# M218X.net
KiCad netlist of a schematic drawn in EAGLE
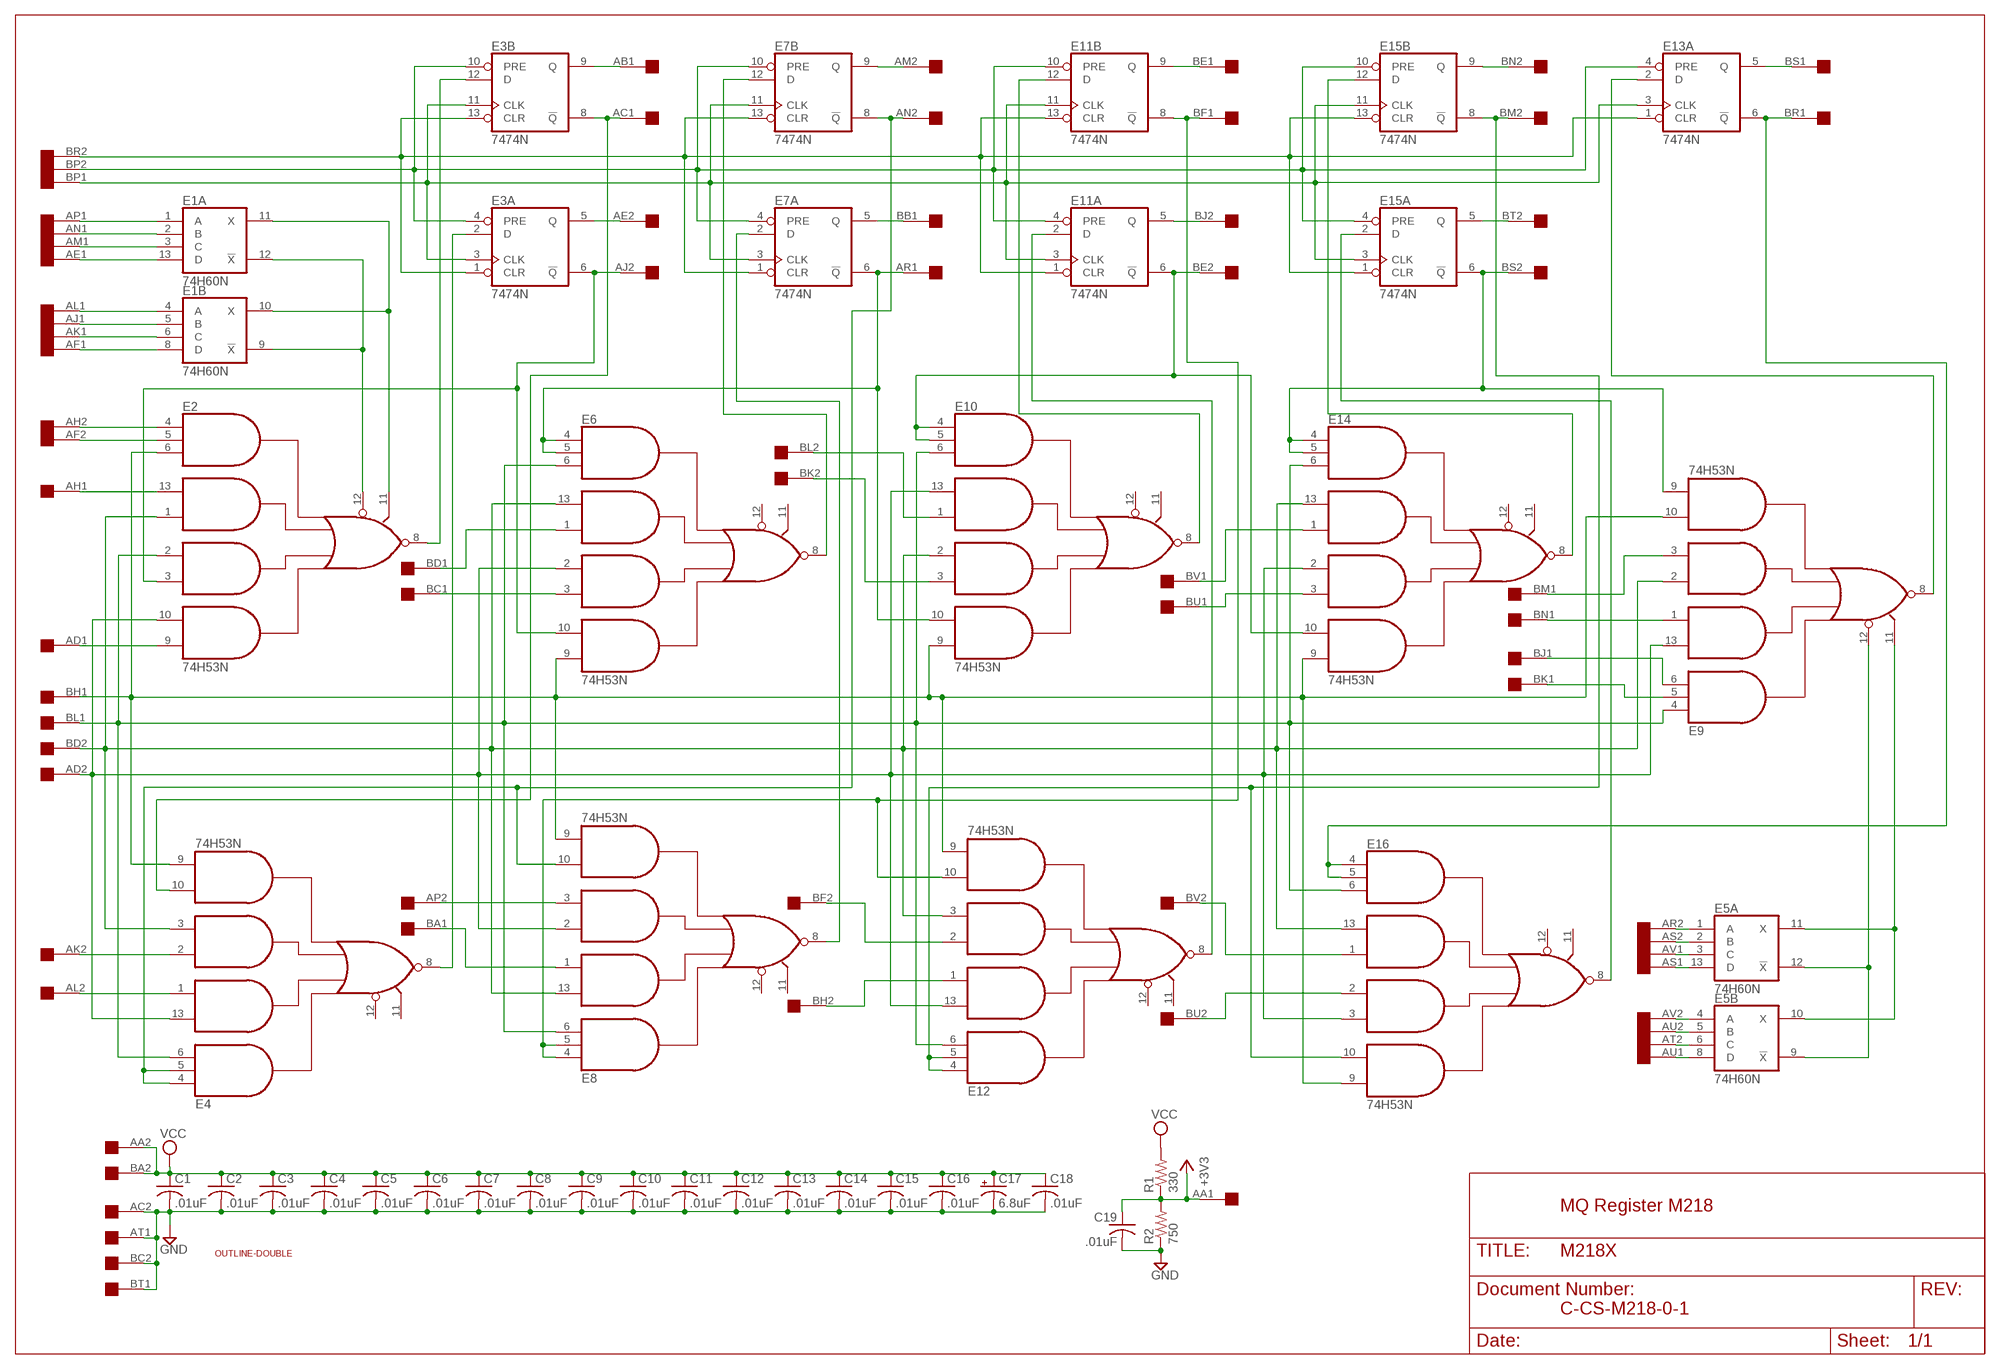
[diagram p0: schematic, sheet 1]

(export (version "E")
  (design (tool "Eeschema 10.0.6"))
  (components
    (comp (ref "C1")
      (value ".01uF")
      (footprint "eagle-import:C050-025X075")
      (libsource (lib "eagle-import") (part "C-US050-025X075"))
    )
    (comp (ref "C2")
      (value ".01uF")
      (footprint "eagle-import:C050-025X075")
      (libsource (lib "eagle-import") (part "C-US050-025X075"))
    )
    (comp (ref "C3")
      (value ".01uF")
      (footprint "eagle-import:C050-025X075")
      (libsource (lib "eagle-import") (part "C-US050-025X075"))
    )
    (comp (ref "C4")
      (value ".01uF")
      (footprint "eagle-import:C050-025X075")
      (libsource (lib "eagle-import") (part "C-US050-025X075"))
    )
    (comp (ref "C5")
      (value ".01uF")
      (footprint "eagle-import:C050-025X075")
      (libsource (lib "eagle-import") (part "C-US050-025X075"))
    )
    (comp (ref "C6")
      (value ".01uF")
      (footprint "eagle-import:C050-025X075")
      (libsource (lib "eagle-import") (part "C-US050-025X075"))
    )
    (comp (ref "C7")
      (value ".01uF")
      (footprint "eagle-import:C050-025X075")
      (libsource (lib "eagle-import") (part "C-US050-025X075"))
    )
    (comp (ref "C8")
      (value ".01uF")
      (footprint "eagle-import:C050-025X075")
      (libsource (lib "eagle-import") (part "C-US050-025X075"))
    )
    (comp (ref "C9")
      (value ".01uF")
      (footprint "eagle-import:C050-025X075")
      (libsource (lib "eagle-import") (part "C-US050-025X075"))
    )
    (comp (ref "C10")
      (value ".01uF")
      (footprint "eagle-import:C050-025X075")
      (libsource (lib "eagle-import") (part "C-US050-025X075"))
    )
    (comp (ref "C11")
      (value ".01uF")
      (footprint "eagle-import:C050-025X075")
      (libsource (lib "eagle-import") (part "C-US050-025X075"))
    )
    (comp (ref "C12")
      (value ".01uF")
      (footprint "eagle-import:C050-025X075")
      (libsource (lib "eagle-import") (part "C-US050-025X075"))
    )
    (comp (ref "C13")
      (value ".01uF")
      (footprint "eagle-import:C050-025X075")
      (libsource (lib "eagle-import") (part "C-US050-025X075"))
    )
    (comp (ref "C14")
      (value ".01uF")
      (footprint "eagle-import:C050-025X075")
      (libsource (lib "eagle-import") (part "C-US050-025X075"))
    )
    (comp (ref "C15")
      (value ".01uF")
      (footprint "eagle-import:C050-025X075")
      (libsource (lib "eagle-import") (part "C-US050-025X075"))
    )
    (comp (ref "C16")
      (value ".01uF")
      (footprint "eagle-import:C050-025X075")
      (libsource (lib "eagle-import") (part "C-US050-025X075"))
    )
    (comp (ref "C17")
      (value "6.8uF")
      (footprint "eagle-import:E12-8")
      (libsource (lib "eagle-import") (part "CPOL-USE20-8AXIAL"))
    )
    (comp (ref "C18")
      (value ".01uF")
      (footprint "eagle-import:C050-025X075")
      (libsource (lib "eagle-import") (part "C-US050-025X075"))
    )
    (comp (ref "C19")
      (value ".01uF")
      (footprint "eagle-import:C050-025X075")
      (libsource (lib "eagle-import") (part "C-US050-025X075"))
    )
    (comp (ref "E1")
      (value "74H60N")
      (footprint "eagle-import:DIL14")
      (libsource (lib "eagle-import") (part "7460N"))
    )
    (comp (ref "E2")
      (value "74H53N")
      (footprint "eagle-import:DIL14")
      (libsource (lib "eagle-import") (part "74H53N"))
    )
    (comp (ref "E3")
      (value "7474N")
      (footprint "eagle-import:DIL14")
      (libsource (lib "eagle-import") (part "7474NS"))
    )
    (comp (ref "E4")
      (value "74H53N")
      (footprint "eagle-import:DIL14")
      (libsource (lib "eagle-import") (part "74H53N"))
    )
    (comp (ref "E5")
      (value "74H60N")
      (footprint "eagle-import:DIL14")
      (libsource (lib "eagle-import") (part "7460N"))
    )
    (comp (ref "E6")
      (value "74H53N")
      (footprint "eagle-import:DIL14")
      (libsource (lib "eagle-import") (part "74H53N"))
    )
    (comp (ref "E7")
      (value "7474N")
      (footprint "eagle-import:DIL14")
      (libsource (lib "eagle-import") (part "7474NS"))
    )
    (comp (ref "E8")
      (value "74H53N")
      (footprint "eagle-import:DIL14")
      (libsource (lib "eagle-import") (part "74H53N"))
    )
    (comp (ref "E9")
      (value "74H53N")
      (footprint "eagle-import:DIL14")
      (libsource (lib "eagle-import") (part "74H53N"))
    )
    (comp (ref "E10")
      (value "74H53N")
      (footprint "eagle-import:DIL14")
      (libsource (lib "eagle-import") (part "74H53N"))
    )
    (comp (ref "E11")
      (value "7474N")
      (footprint "eagle-import:DIL14")
      (libsource (lib "eagle-import") (part "7474NS"))
    )
    (comp (ref "E12")
      (value "74H53N")
      (footprint "eagle-import:DIL14")
      (libsource (lib "eagle-import") (part "74H53N"))
    )
    (comp (ref "E13")
      (value "7474N")
      (footprint "eagle-import:DIL14")
      (libsource (lib "eagle-import") (part "7474NS"))
    )
    (comp (ref "E14")
      (value "74H53N")
      (footprint "eagle-import:DIL14")
      (libsource (lib "eagle-import") (part "74H53N"))
    )
    (comp (ref "E15")
      (value "7474N")
      (footprint "eagle-import:DIL14")
      (libsource (lib "eagle-import") (part "7474NS"))
    )
    (comp (ref "E16")
      (value "74H53N")
      (footprint "eagle-import:DIL14")
      (libsource (lib "eagle-import") (part "74H53N"))
    )
    (comp (ref "R1")
      (value "330")
      (footprint "eagle-import:0207_10")
      (libsource (lib "eagle-import") (part "R-US_0207/10"))
    )
    (comp (ref "R2")
      (value "750")
      (footprint "eagle-import:0207_10")
      (libsource (lib "eagle-import") (part "R-US_0207/10"))
    )
    (comp (ref "U$1")
      (value "OUTLINE-DOUBLE")
      (footprint "eagle-import:DOUBLE")
      (libsource (lib "eagle-import") (part "OUTLINE-DOUBLE"))
    )
    (comp (ref "U$3")
      (value "DOUBLE")
      (footprint "eagle-import:EDGE-CON4")
      (libsource (lib "eagle-import") (part "DOUBLE"))
    )
  )
  (nets
    (net (code "1") (name "+3V3") (class "Default")
      (node (ref "C19") (pin "1") (pinfunction "1_1") (pintype "passive"))
      (node (ref "R1") (pin "1") (pinfunction "1_1") (pintype "passive"))
      (node (ref "R2") (pin "2") (pinfunction "2_2") (pintype "passive"))
      (node (ref "U$3") (pin "AA1") (pinfunction "1_AA1") (pintype "bidirectional"))
    )
    (net (code "2") (name "GND") (class "Default")
      (node (ref "C1") (pin "2") (pinfunction "2_2") (pintype "passive"))
      (node (ref "C10") (pin "2") (pinfunction "2_2") (pintype "passive"))
      (node (ref "C11") (pin "2") (pinfunction "2_2") (pintype "passive"))
      (node (ref "C12") (pin "2") (pinfunction "2_2") (pintype "passive"))
      (node (ref "C13") (pin "2") (pinfunction "2_2") (pintype "passive"))
      (node (ref "C14") (pin "2") (pinfunction "2_2") (pintype "passive"))
      (node (ref "C15") (pin "2") (pinfunction "2_2") (pintype "passive"))
      (node (ref "C16") (pin "2") (pinfunction "2_2") (pintype "passive"))
      (node (ref "C17") (pin "-") (pinfunction "-_-") (pintype "passive"))
      (node (ref "C18") (pin "2") (pinfunction "2_2") (pintype "passive"))
      (node (ref "C19") (pin "2") (pinfunction "2_2") (pintype "passive"))
      (node (ref "C2") (pin "2") (pinfunction "2_2") (pintype "passive"))
      (node (ref "C3") (pin "2") (pinfunction "2_2") (pintype "passive"))
      (node (ref "C4") (pin "2") (pinfunction "2_2") (pintype "passive"))
      (node (ref "C5") (pin "2") (pinfunction "2_2") (pintype "passive"))
      (node (ref "C6") (pin "2") (pinfunction "2_2") (pintype "passive"))
      (node (ref "C7") (pin "2") (pinfunction "2_2") (pintype "passive"))
      (node (ref "C8") (pin "2") (pinfunction "2_2") (pintype "passive"))
      (node (ref "C9") (pin "2") (pinfunction "2_2") (pintype "passive"))
      (node (ref "R2") (pin "1") (pinfunction "1_1") (pintype "passive"))
      (node (ref "U$3") (pin "AC2") (pinfunction "1_AC2") (pintype "bidirectional"))
      (node (ref "U$3") (pin "AT1") (pinfunction "1_AT1") (pintype "bidirectional"))
      (node (ref "U$3") (pin "BC2") (pinfunction "1_BC2") (pintype "bidirectional"))
      (node (ref "U$3") (pin "BT1") (pinfunction "1_BT1") (pintype "bidirectional"))
    )
    (net (code "3") (name "Net-(E1A-A)") (class "Default")
      (node (ref "E1") (pin "1") (pinfunction "A_1") (pintype "input"))
      (node (ref "U$3") (pin "AP1") (pinfunction "1_AP1") (pintype "bidirectional"))
    )
    (net (code "4") (name "Net-(E1A-B)") (class "Default")
      (node (ref "E1") (pin "2") (pinfunction "B_2") (pintype "input"))
      (node (ref "U$3") (pin "AN1") (pinfunction "1_AN1") (pintype "bidirectional"))
    )
    (net (code "5") (name "Net-(E1A-C)") (class "Default")
      (node (ref "E1") (pin "3") (pinfunction "C_3") (pintype "input"))
      (node (ref "U$3") (pin "AM1") (pinfunction "1_AM1") (pintype "bidirectional"))
    )
    (net (code "6") (name "Net-(E1A-D)") (class "Default")
      (node (ref "E1") (pin "13") (pinfunction "D_13") (pintype "input"))
      (node (ref "U$3") (pin "AE1") (pinfunction "1_AE1") (pintype "bidirectional"))
    )
    (net (code "7") (name "Net-(E1A-X)") (class "Default")
      (node (ref "E1") (pin "10") (pinfunction "X_10") (pintype "output"))
      (node (ref "E1") (pin "11") (pinfunction "X_11") (pintype "output"))
      (node (ref "E2") (pin "11") (pinfunction "I10_11") (pintype "passive"))
    )
    (net (code "8") (name "Net-(E1A-~{X})") (class "Default")
      (node (ref "E1") (pin "12") (pinfunction "~{X}_12") (pintype "output"))
      (node (ref "E1") (pin "9") (pinfunction "~{X}_9") (pintype "output"))
      (node (ref "E2") (pin "12") (pinfunction "I9_12") (pintype "passive"))
    )
    (net (code "9") (name "Net-(E1B-A)") (class "Default")
      (node (ref "E1") (pin "4") (pinfunction "A_4") (pintype "input"))
      (node (ref "U$3") (pin "AL1") (pinfunction "1_AL1") (pintype "bidirectional"))
    )
    (net (code "10") (name "Net-(E1B-B)") (class "Default")
      (node (ref "E1") (pin "5") (pinfunction "B_5") (pintype "input"))
      (node (ref "U$3") (pin "AJ1") (pinfunction "1_AJ1") (pintype "bidirectional"))
    )
    (net (code "11") (name "Net-(E1B-C)") (class "Default")
      (node (ref "E1") (pin "6") (pinfunction "C_6") (pintype "input"))
      (node (ref "U$3") (pin "AK1") (pinfunction "1_AK1") (pintype "bidirectional"))
    )
    (net (code "12") (name "Net-(E1B-D)") (class "Default")
      (node (ref "E1") (pin "8") (pinfunction "D_8") (pintype "input"))
      (node (ref "U$3") (pin "AF1") (pinfunction "1_AF1") (pintype "bidirectional"))
    )
    (net (code "13") (name "Net-(E2A-I1)") (class "Default")
      (node (ref "E2") (pin "4") (pinfunction "I1_4") (pintype "input"))
      (node (ref "U$3") (pin "AH2") (pinfunction "1_AH2") (pintype "bidirectional"))
    )
    (net (code "14") (name "Net-(E2A-I3)") (class "Default")
      (node (ref "E2") (pin "13") (pinfunction "I3_13") (pintype "input"))
      (node (ref "U$3") (pin "AH1") (pinfunction "1_AH1") (pintype "bidirectional"))
    )
    (net (code "15") (name "Net-(E2A-I6)") (class "Default")
      (node (ref "E2") (pin "3") (pinfunction "I6_3") (pintype "input"))
      (node (ref "E3") (pin "6") (pinfunction "~{Q}_6") (pintype "output"))
      (node (ref "E6") (pin "10") (pinfunction "I7_10") (pintype "input"))
      (node (ref "U$3") (pin "AJ2") (pinfunction "1_AJ2") (pintype "bidirectional"))
    )
    (net (code "16") (name "Net-(E2A-I8)") (class "Default")
      (node (ref "E2") (pin "9") (pinfunction "I8_9") (pintype "input"))
      (node (ref "U$3") (pin "AD1") (pinfunction "1_AD1") (pintype "bidirectional"))
    )
    (net (code "17") (name "Net-(E2A-I11)") (class "Default")
      (node (ref "E2") (pin "5") (pinfunction "I11_5") (pintype "input"))
      (node (ref "U$3") (pin "AF2") (pinfunction "1_AF2") (pintype "bidirectional"))
    )
    (net (code "18") (name "Net-(E2A-O)") (class "Default")
      (node (ref "E2") (pin "8") (pinfunction "O_8") (pintype "output"))
      (node (ref "E3") (pin "12") (pinfunction "D_12") (pintype "input"))
    )
    (net (code "19") (name "Net-(E3A-D)") (class "Default")
      (node (ref "E3") (pin "2") (pinfunction "D_2") (pintype "input"))
      (node (ref "E4") (pin "8") (pinfunction "O_8") (pintype "output"))
    )
    (net (code "20") (name "Net-(E3A-Q)") (class "Default")
      (node (ref "E3") (pin "5") (pinfunction "Q_5") (pintype "output"))
      (node (ref "U$3") (pin "AE2") (pinfunction "1_AE2") (pintype "bidirectional"))
    )
    (net (code "21") (name "Net-(E3B-Q)") (class "Default")
      (node (ref "E3") (pin "9") (pinfunction "Q_9") (pintype "output"))
      (node (ref "U$3") (pin "AB1") (pinfunction "1_AB1") (pintype "bidirectional"))
    )
    (net (code "22") (name "Net-(E3B-~{Q})") (class "Default")
      (node (ref "E3") (pin "8") (pinfunction "~{Q}_8") (pintype "output"))
      (node (ref "E4") (pin "10") (pinfunction "I7_10") (pintype "input"))
      (node (ref "U$3") (pin "AC1") (pinfunction "1_AC1") (pintype "bidirectional"))
    )
    (net (code "23") (name "Net-(E4A-I1)") (class "Default")
      (node (ref "E4") (pin "4") (pinfunction "I1_4") (pintype "input"))
      (node (ref "E4") (pin "5") (pinfunction "I11_5") (pintype "input"))
      (node (ref "E7") (pin "8") (pinfunction "~{Q}_8") (pintype "output"))
      (node (ref "E8") (pin "10") (pinfunction "I7_10") (pintype "input"))
      (node (ref "U$3") (pin "AN2") (pinfunction "1_AN2") (pintype "bidirectional"))
    )
    (net (code "24") (name "Net-(E4A-I4)") (class "Default")
      (node (ref "E4") (pin "1") (pinfunction "I4_1") (pintype "input"))
      (node (ref "U$3") (pin "AL2") (pinfunction "1_AL2") (pintype "bidirectional"))
    )
    (net (code "25") (name "Net-(E4A-I5)") (class "Default")
      (node (ref "E4") (pin "2") (pinfunction "I5_2") (pintype "input"))
      (node (ref "U$3") (pin "AK2") (pinfunction "1_AK2") (pintype "bidirectional"))
    )
    (net (code "26") (name "Net-(E5A-A)") (class "Default")
      (node (ref "E5") (pin "1") (pinfunction "A_1") (pintype "input"))
      (node (ref "U$3") (pin "AR2") (pinfunction "1_AR2") (pintype "bidirectional"))
    )
    (net (code "27") (name "Net-(E5A-B)") (class "Default")
      (node (ref "E5") (pin "2") (pinfunction "B_2") (pintype "input"))
      (node (ref "U$3") (pin "AS2") (pinfunction "1_AS2") (pintype "bidirectional"))
    )
    (net (code "28") (name "Net-(E5A-C)") (class "Default")
      (node (ref "E5") (pin "3") (pinfunction "C_3") (pintype "input"))
      (node (ref "U$3") (pin "AV1") (pinfunction "1_AV1") (pintype "bidirectional"))
    )
    (net (code "29") (name "Net-(E5A-D)") (class "Default")
      (node (ref "E5") (pin "13") (pinfunction "D_13") (pintype "input"))
      (node (ref "U$3") (pin "AS1") (pinfunction "1_AS1") (pintype "bidirectional"))
    )
    (net (code "30") (name "Net-(E5A-X)") (class "Default")
      (node (ref "E5") (pin "10") (pinfunction "X_10") (pintype "output"))
      (node (ref "E5") (pin "11") (pinfunction "X_11") (pintype "output"))
      (node (ref "E9") (pin "11") (pinfunction "I10_11") (pintype "passive"))
    )
    (net (code "31") (name "Net-(E5A-~{X})") (class "Default")
      (node (ref "E5") (pin "12") (pinfunction "~{X}_12") (pintype "output"))
      (node (ref "E5") (pin "9") (pinfunction "~{X}_9") (pintype "output"))
      (node (ref "E9") (pin "12") (pinfunction "I9_12") (pintype "passive"))
    )
    (net (code "32") (name "Net-(E5B-A)") (class "Default")
      (node (ref "E5") (pin "4") (pinfunction "A_4") (pintype "input"))
      (node (ref "U$3") (pin "AV2") (pinfunction "1_AV2") (pintype "bidirectional"))
    )
    (net (code "33") (name "Net-(E5B-B)") (class "Default")
      (node (ref "E5") (pin "5") (pinfunction "B_5") (pintype "input"))
      (node (ref "U$3") (pin "AU2") (pinfunction "1_AU2") (pintype "bidirectional"))
    )
    (net (code "34") (name "Net-(E5B-C)") (class "Default")
      (node (ref "E5") (pin "6") (pinfunction "C_6") (pintype "input"))
      (node (ref "U$3") (pin "AT2") (pinfunction "1_AT2") (pintype "bidirectional"))
    )
    (net (code "35") (name "Net-(E5B-D)") (class "Default")
      (node (ref "E5") (pin "8") (pinfunction "D_8") (pintype "input"))
      (node (ref "U$3") (pin "AU1") (pinfunction "1_AU1") (pintype "bidirectional"))
    )
    (net (code "36") (name "Net-(E6A-I4)") (class "Default")
      (node (ref "E6") (pin "1") (pinfunction "I4_1") (pintype "input"))
      (node (ref "U$3") (pin "BD1") (pinfunction "1_BD1") (pintype "bidirectional"))
    )
    (net (code "37") (name "Net-(E6A-I6)") (class "Default")
      (node (ref "E6") (pin "3") (pinfunction "I6_3") (pintype "input"))
      (node (ref "U$3") (pin "BC1") (pinfunction "1_BC1") (pintype "bidirectional"))
    )
    (net (code "38") (name "Net-(E6A-O)") (class "Default")
      (node (ref "E6") (pin "8") (pinfunction "O_8") (pintype "output"))
      (node (ref "E7") (pin "12") (pinfunction "D_12") (pintype "input"))
    )
    (net (code "39") (name "Net-(E7A-D)") (class "Default")
      (node (ref "E7") (pin "2") (pinfunction "D_2") (pintype "input"))
      (node (ref "E8") (pin "8") (pinfunction "O_8") (pintype "output"))
    )
    (net (code "40") (name "Net-(E7A-Q)") (class "Default")
      (node (ref "E7") (pin "5") (pinfunction "Q_5") (pintype "output"))
      (node (ref "U$3") (pin "BB1") (pinfunction "1_BB1") (pintype "bidirectional"))
    )
    (net (code "41") (name "Net-(E7B-Q)") (class "Default")
      (node (ref "E7") (pin "9") (pinfunction "Q_9") (pintype "output"))
      (node (ref "U$3") (pin "AM2") (pinfunction "1_AM2") (pintype "bidirectional"))
    )
    (net (code "42") (name "Net-(E8A-I4)") (class "Default")
      (node (ref "E8") (pin "1") (pinfunction "I4_1") (pintype "input"))
      (node (ref "U$3") (pin "BA1") (pinfunction "1_BA1") (pintype "bidirectional"))
    )
    (net (code "43") (name "Net-(E8A-I6)") (class "Default")
      (node (ref "E8") (pin "3") (pinfunction "I6_3") (pintype "input"))
      (node (ref "U$3") (pin "AP2") (pinfunction "1_AP2") (pintype "bidirectional"))
    )
    (net (code "44") (name "Net-(E9A-I2)") (class "Default")
      (node (ref "E9") (pin "6") (pinfunction "I2_6") (pintype "input"))
      (node (ref "U$3") (pin "BJ1") (pinfunction "1_BJ1") (pintype "bidirectional"))
    )
    (net (code "45") (name "Net-(E9A-I4)") (class "Default")
      (node (ref "E9") (pin "1") (pinfunction "I4_1") (pintype "input"))
      (node (ref "U$3") (pin "BN1") (pinfunction "1_BN1") (pintype "bidirectional"))
    )
    (net (code "46") (name "Net-(E9A-I6)") (class "Default")
      (node (ref "E9") (pin "3") (pinfunction "I6_3") (pintype "input"))
      (node (ref "U$3") (pin "BM1") (pinfunction "1_BM1") (pintype "bidirectional"))
    )
    (net (code "47") (name "Net-(E9A-I11)") (class "Default")
      (node (ref "E9") (pin "5") (pinfunction "I11_5") (pintype "input"))
      (node (ref "U$3") (pin "BK1") (pinfunction "1_BK1") (pintype "bidirectional"))
    )
    (net (code "48") (name "Net-(E10A-I1)") (class "Default")
      (node (ref "E10") (pin "4") (pinfunction "I1_4") (pintype "input"))
      (node (ref "E10") (pin "5") (pinfunction "I11_5") (pintype "input"))
      (node (ref "E11") (pin "6") (pinfunction "~{Q}_6") (pintype "output"))
      (node (ref "E14") (pin "10") (pinfunction "I7_10") (pintype "input"))
      (node (ref "U$3") (pin "BE2") (pinfunction "1_BE2") (pintype "bidirectional"))
    )
    (net (code "49") (name "Net-(E10A-I2)") (class "Default")
      (node (ref "E10") (pin "6") (pinfunction "I2_6") (pintype "input"))
      (node (ref "E12") (pin "6") (pinfunction "I2_6") (pintype "input"))
      (node (ref "E14") (pin "6") (pinfunction "I2_6") (pintype "input"))
      (node (ref "E16") (pin "6") (pinfunction "I2_6") (pintype "input"))
      (node (ref "E2") (pin "2") (pinfunction "I5_2") (pintype "input"))
      (node (ref "E4") (pin "6") (pinfunction "I2_6") (pintype "input"))
      (node (ref "E6") (pin "6") (pinfunction "I2_6") (pintype "input"))
      (node (ref "E8") (pin "6") (pinfunction "I2_6") (pintype "input"))
      (node (ref "E9") (pin "4") (pinfunction "I1_4") (pintype "input"))
      (node (ref "U$3") (pin "BL1") (pinfunction "1_BL1") (pintype "bidirectional"))
    )
    (net (code "50") (name "Net-(E10A-I3)") (class "Default")
      (node (ref "E10") (pin "13") (pinfunction "I3_13") (pintype "input"))
      (node (ref "E12") (pin "13") (pinfunction "I3_13") (pintype "input"))
      (node (ref "E14") (pin "2") (pinfunction "I5_2") (pintype "input"))
      (node (ref "E16") (pin "3") (pinfunction "I6_3") (pintype "input"))
      (node (ref "E2") (pin "10") (pinfunction "I7_10") (pintype "input"))
      (node (ref "E4") (pin "13") (pinfunction "I3_13") (pintype "input"))
      (node (ref "E6") (pin "2") (pinfunction "I5_2") (pintype "input"))
      (node (ref "E8") (pin "2") (pinfunction "I5_2") (pintype "input"))
      (node (ref "E9") (pin "13") (pinfunction "I3_13") (pintype "input"))
      (node (ref "U$3") (pin "AD2") (pinfunction "1_AD2") (pintype "bidirectional"))
    )
    (net (code "51") (name "Net-(E10A-I4)") (class "Default")
      (node (ref "E10") (pin "1") (pinfunction "I4_1") (pintype "input"))
      (node (ref "U$3") (pin "BL2") (pinfunction "1_BL2") (pintype "bidirectional"))
    )
    (net (code "52") (name "Net-(E10A-I5)") (class "Default")
      (node (ref "E10") (pin "2") (pinfunction "I5_2") (pintype "input"))
      (node (ref "E12") (pin "3") (pinfunction "I6_3") (pintype "input"))
      (node (ref "E14") (pin "13") (pinfunction "I3_13") (pintype "input"))
      (node (ref "E16") (pin "13") (pinfunction "I3_13") (pintype "input"))
      (node (ref "E2") (pin "1") (pinfunction "I4_1") (pintype "input"))
      (node (ref "E4") (pin "3") (pinfunction "I6_3") (pintype "input"))
      (node (ref "E6") (pin "13") (pinfunction "I3_13") (pintype "input"))
      (node (ref "E8") (pin "13") (pinfunction "I3_13") (pintype "input"))
      (node (ref "E9") (pin "2") (pinfunction "I5_2") (pintype "input"))
      (node (ref "U$3") (pin "BD2") (pinfunction "1_BD2") (pintype "bidirectional"))
    )
    (net (code "53") (name "Net-(E10A-I6)") (class "Default")
      (node (ref "E10") (pin "3") (pinfunction "I6_3") (pintype "input"))
      (node (ref "U$3") (pin "BK2") (pinfunction "1_BK2") (pintype "bidirectional"))
    )
    (net (code "54") (name "Net-(E10A-I7)") (class "Default")
      (node (ref "E10") (pin "10") (pinfunction "I7_10") (pintype "input"))
      (node (ref "E6") (pin "4") (pinfunction "I1_4") (pintype "input"))
      (node (ref "E6") (pin "5") (pinfunction "I11_5") (pintype "input"))
      (node (ref "E7") (pin "6") (pinfunction "~{Q}_6") (pintype "output"))
      (node (ref "U$3") (pin "AR1") (pinfunction "1_AR1") (pintype "bidirectional"))
    )
    (net (code "55") (name "Net-(E10A-I8)") (class "Default")
      (node (ref "E10") (pin "9") (pinfunction "I8_9") (pintype "input"))
      (node (ref "E12") (pin "9") (pinfunction "I8_9") (pintype "input"))
      (node (ref "E14") (pin "9") (pinfunction "I8_9") (pintype "input"))
      (node (ref "E16") (pin "9") (pinfunction "I8_9") (pintype "input"))
      (node (ref "E2") (pin "6") (pinfunction "I2_6") (pintype "input"))
      (node (ref "E4") (pin "9") (pinfunction "I8_9") (pintype "input"))
      (node (ref "E6") (pin "9") (pinfunction "I8_9") (pintype "input"))
      (node (ref "E8") (pin "9") (pinfunction "I8_9") (pintype "input"))
      (node (ref "E9") (pin "10") (pinfunction "I7_10") (pintype "input"))
      (node (ref "U$3") (pin "BH1") (pinfunction "1_BH1") (pintype "bidirectional"))
    )
    (net (code "56") (name "Net-(E10A-O)") (class "Default")
      (node (ref "E10") (pin "8") (pinfunction "O_8") (pintype "output"))
      (node (ref "E11") (pin "12") (pinfunction "D_12") (pintype "input"))
    )
    (net (code "57") (name "Net-(E11A-CLK)") (class "Default")
      (node (ref "E11") (pin "11") (pinfunction "CLK_11") (pintype "input"))
      (node (ref "E11") (pin "3") (pinfunction "CLK_3") (pintype "input"))
      (node (ref "E13") (pin "3") (pinfunction "CLK_3") (pintype "input"))
      (node (ref "E15") (pin "11") (pinfunction "CLK_11") (pintype "input"))
      (node (ref "E15") (pin "3") (pinfunction "CLK_3") (pintype "input"))
      (node (ref "E3") (pin "11") (pinfunction "CLK_11") (pintype "input"))
      (node (ref "E3") (pin "3") (pinfunction "CLK_3") (pintype "input"))
      (node (ref "E7") (pin "11") (pinfunction "CLK_11") (pintype "input"))
      (node (ref "E7") (pin "3") (pinfunction "CLK_3") (pintype "input"))
      (node (ref "U$3") (pin "BP1") (pinfunction "1_BP1") (pintype "bidirectional"))
    )
    (net (code "58") (name "Net-(E11A-CLR)") (class "Default")
      (node (ref "E11") (pin "1") (pinfunction "CLR_1") (pintype "input"))
      (node (ref "E11") (pin "13") (pinfunction "CLR_13") (pintype "input"))
      (node (ref "E13") (pin "1") (pinfunction "CLR_1") (pintype "input"))
      (node (ref "E15") (pin "1") (pinfunction "CLR_1") (pintype "input"))
      (node (ref "E15") (pin "13") (pinfunction "CLR_13") (pintype "input"))
      (node (ref "E3") (pin "1") (pinfunction "CLR_1") (pintype "input"))
      (node (ref "E3") (pin "13") (pinfunction "CLR_13") (pintype "input"))
      (node (ref "E7") (pin "1") (pinfunction "CLR_1") (pintype "input"))
      (node (ref "E7") (pin "13") (pinfunction "CLR_13") (pintype "input"))
      (node (ref "U$3") (pin "BR2") (pinfunction "1_BR2") (pintype "bidirectional"))
    )
    (net (code "59") (name "Net-(E11A-D)") (class "Default")
      (node (ref "E11") (pin "2") (pinfunction "D_2") (pintype "input"))
      (node (ref "E12") (pin "8") (pinfunction "O_8") (pintype "output"))
    )
    (net (code "60") (name "Net-(E11A-PRE)") (class "Default")
      (node (ref "E11") (pin "10") (pinfunction "PRE_10") (pintype "input"))
      (node (ref "E11") (pin "4") (pinfunction "PRE_4") (pintype "input"))
      (node (ref "E13") (pin "4") (pinfunction "PRE_4") (pintype "input"))
      (node (ref "E15") (pin "10") (pinfunction "PRE_10") (pintype "input"))
      (node (ref "E15") (pin "4") (pinfunction "PRE_4") (pintype "input"))
      (node (ref "E3") (pin "10") (pinfunction "PRE_10") (pintype "input"))
      (node (ref "E3") (pin "4") (pinfunction "PRE_4") (pintype "input"))
      (node (ref "E7") (pin "10") (pinfunction "PRE_10") (pintype "input"))
      (node (ref "E7") (pin "4") (pinfunction "PRE_4") (pintype "input"))
      (node (ref "U$3") (pin "BP2") (pinfunction "1_BP2") (pintype "bidirectional"))
    )
    (net (code "61") (name "Net-(E11A-Q)") (class "Default")
      (node (ref "E11") (pin "5") (pinfunction "Q_5") (pintype "output"))
      (node (ref "U$3") (pin "BJ2") (pinfunction "1_BJ2") (pintype "bidirectional"))
    )
    (net (code "62") (name "Net-(E11B-Q)") (class "Default")
      (node (ref "E11") (pin "9") (pinfunction "Q_9") (pintype "output"))
      (node (ref "U$3") (pin "BE1") (pinfunction "1_BE1") (pintype "bidirectional"))
    )
    (net (code "63") (name "Net-(E11B-~{Q})") (class "Default")
      (node (ref "E11") (pin "8") (pinfunction "~{Q}_8") (pintype "output"))
      (node (ref "E12") (pin "10") (pinfunction "I7_10") (pintype "input"))
      (node (ref "E8") (pin "4") (pinfunction "I1_4") (pintype "input"))
      (node (ref "E8") (pin "5") (pinfunction "I11_5") (pintype "input"))
      (node (ref "U$3") (pin "BF1") (pinfunction "1_BF1") (pintype "bidirectional"))
    )
    (net (code "64") (name "Net-(E12A-I1)") (class "Default")
      (node (ref "E12") (pin "4") (pinfunction "I1_4") (pintype "input"))
      (node (ref "E12") (pin "5") (pinfunction "I11_5") (pintype "input"))
      (node (ref "E15") (pin "8") (pinfunction "~{Q}_8") (pintype "output"))
      (node (ref "E16") (pin "10") (pinfunction "I7_10") (pintype "input"))
      (node (ref "U$3") (pin "BM2") (pinfunction "1_BM2") (pintype "bidirectional"))
    )
    (net (code "65") (name "Net-(E12A-I4)") (class "Default")
      (node (ref "E12") (pin "1") (pinfunction "I4_1") (pintype "input"))
      (node (ref "U$3") (pin "BH2") (pinfunction "1_BH2") (pintype "bidirectional"))
    )
    (net (code "66") (name "Net-(E12A-I5)") (class "Default")
      (node (ref "E12") (pin "2") (pinfunction "I5_2") (pintype "input"))
      (node (ref "U$3") (pin "BF2") (pinfunction "1_BF2") (pintype "bidirectional"))
    )
    (net (code "67") (name "Net-(E13A-D)") (class "Default")
      (node (ref "E13") (pin "2") (pinfunction "D_2") (pintype "input"))
      (node (ref "E9") (pin "8") (pinfunction "O_8") (pintype "output"))
    )
    (net (code "68") (name "Net-(E13A-Q)") (class "Default")
      (node (ref "E13") (pin "5") (pinfunction "Q_5") (pintype "output"))
      (node (ref "U$3") (pin "BS1") (pinfunction "1_BS1") (pintype "bidirectional"))
    )
    (net (code "69") (name "Net-(E13A-~{Q})") (class "Default")
      (node (ref "E13") (pin "6") (pinfunction "~{Q}_6") (pintype "output"))
      (node (ref "E16") (pin "4") (pinfunction "I1_4") (pintype "input"))
      (node (ref "E16") (pin "5") (pinfunction "I11_5") (pintype "input"))
      (node (ref "U$3") (pin "BR1") (pinfunction "1_BR1") (pintype "bidirectional"))
    )
    (net (code "70") (name "Net-(E14A-I1)") (class "Default")
      (node (ref "E14") (pin "4") (pinfunction "I1_4") (pintype "input"))
      (node (ref "E14") (pin "5") (pinfunction "I11_5") (pintype "input"))
      (node (ref "E15") (pin "6") (pinfunction "~{Q}_6") (pintype "output"))
      (node (ref "E9") (pin "9") (pinfunction "I8_9") (pintype "input"))
      (node (ref "U$3") (pin "BS2") (pinfunction "1_BS2") (pintype "bidirectional"))
    )
    (net (code "71") (name "Net-(E14A-I4)") (class "Default")
      (node (ref "E14") (pin "1") (pinfunction "I4_1") (pintype "input"))
      (node (ref "U$3") (pin "BV1") (pinfunction "1_BV1") (pintype "bidirectional"))
    )
    (net (code "72") (name "Net-(E14A-I6)") (class "Default")
      (node (ref "E14") (pin "3") (pinfunction "I6_3") (pintype "input"))
      (node (ref "U$3") (pin "BU1") (pinfunction "1_BU1") (pintype "bidirectional"))
    )
    (net (code "73") (name "Net-(E14A-O)") (class "Default")
      (node (ref "E14") (pin "8") (pinfunction "O_8") (pintype "output"))
      (node (ref "E15") (pin "12") (pinfunction "D_12") (pintype "input"))
    )
    (net (code "74") (name "Net-(E15A-D)") (class "Default")
      (node (ref "E15") (pin "2") (pinfunction "D_2") (pintype "input"))
      (node (ref "E16") (pin "8") (pinfunction "O_8") (pintype "output"))
    )
    (net (code "75") (name "Net-(E15A-Q)") (class "Default")
      (node (ref "E15") (pin "5") (pinfunction "Q_5") (pintype "output"))
      (node (ref "U$3") (pin "BT2") (pinfunction "1_BT2") (pintype "bidirectional"))
    )
    (net (code "76") (name "Net-(E15B-Q)") (class "Default")
      (node (ref "E15") (pin "9") (pinfunction "Q_9") (pintype "output"))
      (node (ref "U$3") (pin "BN2") (pinfunction "1_BN2") (pintype "bidirectional"))
    )
    (net (code "77") (name "Net-(E16A-I4)") (class "Default")
      (node (ref "E16") (pin "1") (pinfunction "I4_1") (pintype "input"))
      (node (ref "U$3") (pin "BV2") (pinfunction "1_BV2") (pintype "bidirectional"))
    )
    (net (code "78") (name "Net-(E16A-I5)") (class "Default")
      (node (ref "E16") (pin "2") (pinfunction "I5_2") (pintype "input"))
      (node (ref "U$3") (pin "BU2") (pinfunction "1_BU2") (pintype "bidirectional"))
    )
    (net (code "79") (name "VCC") (class "Default")
      (node (ref "C1") (pin "1") (pinfunction "1_1") (pintype "passive"))
      (node (ref "C10") (pin "1") (pinfunction "1_1") (pintype "passive"))
      (node (ref "C11") (pin "1") (pinfunction "1_1") (pintype "passive"))
      (node (ref "C12") (pin "1") (pinfunction "1_1") (pintype "passive"))
      (node (ref "C13") (pin "1") (pinfunction "1_1") (pintype "passive"))
      (node (ref "C14") (pin "1") (pinfunction "1_1") (pintype "passive"))
      (node (ref "C15") (pin "1") (pinfunction "1_1") (pintype "passive"))
      (node (ref "C16") (pin "1") (pinfunction "1_1") (pintype "passive"))
      (node (ref "C17") (pin "+") (pinfunction "+_+") (pintype "passive"))
      (node (ref "C18") (pin "1") (pinfunction "1_1") (pintype "passive"))
      (node (ref "C2") (pin "1") (pinfunction "1_1") (pintype "passive"))
      (node (ref "C3") (pin "1") (pinfunction "1_1") (pintype "passive"))
      (node (ref "C4") (pin "1") (pinfunction "1_1") (pintype "passive"))
      (node (ref "C5") (pin "1") (pinfunction "1_1") (pintype "passive"))
      (node (ref "C6") (pin "1") (pinfunction "1_1") (pintype "passive"))
      (node (ref "C7") (pin "1") (pinfunction "1_1") (pintype "passive"))
      (node (ref "C8") (pin "1") (pinfunction "1_1") (pintype "passive"))
      (node (ref "C9") (pin "1") (pinfunction "1_1") (pintype "passive"))
      (node (ref "R1") (pin "2") (pinfunction "2_2") (pintype "passive"))
      (node (ref "U$3") (pin "AA2") (pinfunction "1_AA2") (pintype "bidirectional"))
      (node (ref "U$3") (pin "BA2") (pinfunction "1_BA2") (pintype "bidirectional"))
    )
    (net (code "80") (name "unconnected-(E4A-I9-Pad12)") (class "Default")
      (node (ref "E4") (pin "12") (pinfunction "I9_12") (pintype "passive"))
    )
    (net (code "81") (name "unconnected-(E4A-I10-Pad11)") (class "Default")
      (node (ref "E4") (pin "11") (pinfunction "I10_11") (pintype "passive"))
    )
    (net (code "82") (name "unconnected-(E6A-I9-Pad12)") (class "Default")
      (node (ref "E6") (pin "12") (pinfunction "I9_12") (pintype "passive"))
    )
    (net (code "83") (name "unconnected-(E6A-I10-Pad11)") (class "Default")
      (node (ref "E6") (pin "11") (pinfunction "I10_11") (pintype "passive"))
    )
    (net (code "84") (name "unconnected-(E8A-I9-Pad12)") (class "Default")
      (node (ref "E8") (pin "12") (pinfunction "I9_12") (pintype "passive"))
    )
    (net (code "85") (name "unconnected-(E8A-I10-Pad11)") (class "Default")
      (node (ref "E8") (pin "11") (pinfunction "I10_11") (pintype "passive"))
    )
    (net (code "86") (name "unconnected-(E10A-I9-Pad12)") (class "Default")
      (node (ref "E10") (pin "12") (pinfunction "I9_12") (pintype "passive"))
    )
    (net (code "87") (name "unconnected-(E10A-I10-Pad11)") (class "Default")
      (node (ref "E10") (pin "11") (pinfunction "I10_11") (pintype "passive"))
    )
    (net (code "88") (name "unconnected-(E12A-I9-Pad12)") (class "Default")
      (node (ref "E12") (pin "12") (pinfunction "I9_12") (pintype "passive"))
    )
    (net (code "89") (name "unconnected-(E12A-I10-Pad11)") (class "Default")
      (node (ref "E12") (pin "11") (pinfunction "I10_11") (pintype "passive"))
    )
    (net (code "90") (name "unconnected-(E14A-I9-Pad12)") (class "Default")
      (node (ref "E14") (pin "12") (pinfunction "I9_12") (pintype "passive"))
    )
    (net (code "91") (name "unconnected-(E14A-I10-Pad11)") (class "Default")
      (node (ref "E14") (pin "11") (pinfunction "I10_11") (pintype "passive"))
    )
    (net (code "92") (name "unconnected-(E16A-I9-Pad12)") (class "Default")
      (node (ref "E16") (pin "12") (pinfunction "I9_12") (pintype "passive"))
    )
    (net (code "93") (name "unconnected-(E16A-I10-Pad11)") (class "Default")
      (node (ref "E16") (pin "11") (pinfunction "I10_11") (pintype "passive"))
    )
  )
)
